# MCU.net
KiCad netlist of a schematic drawn in Altium Designer
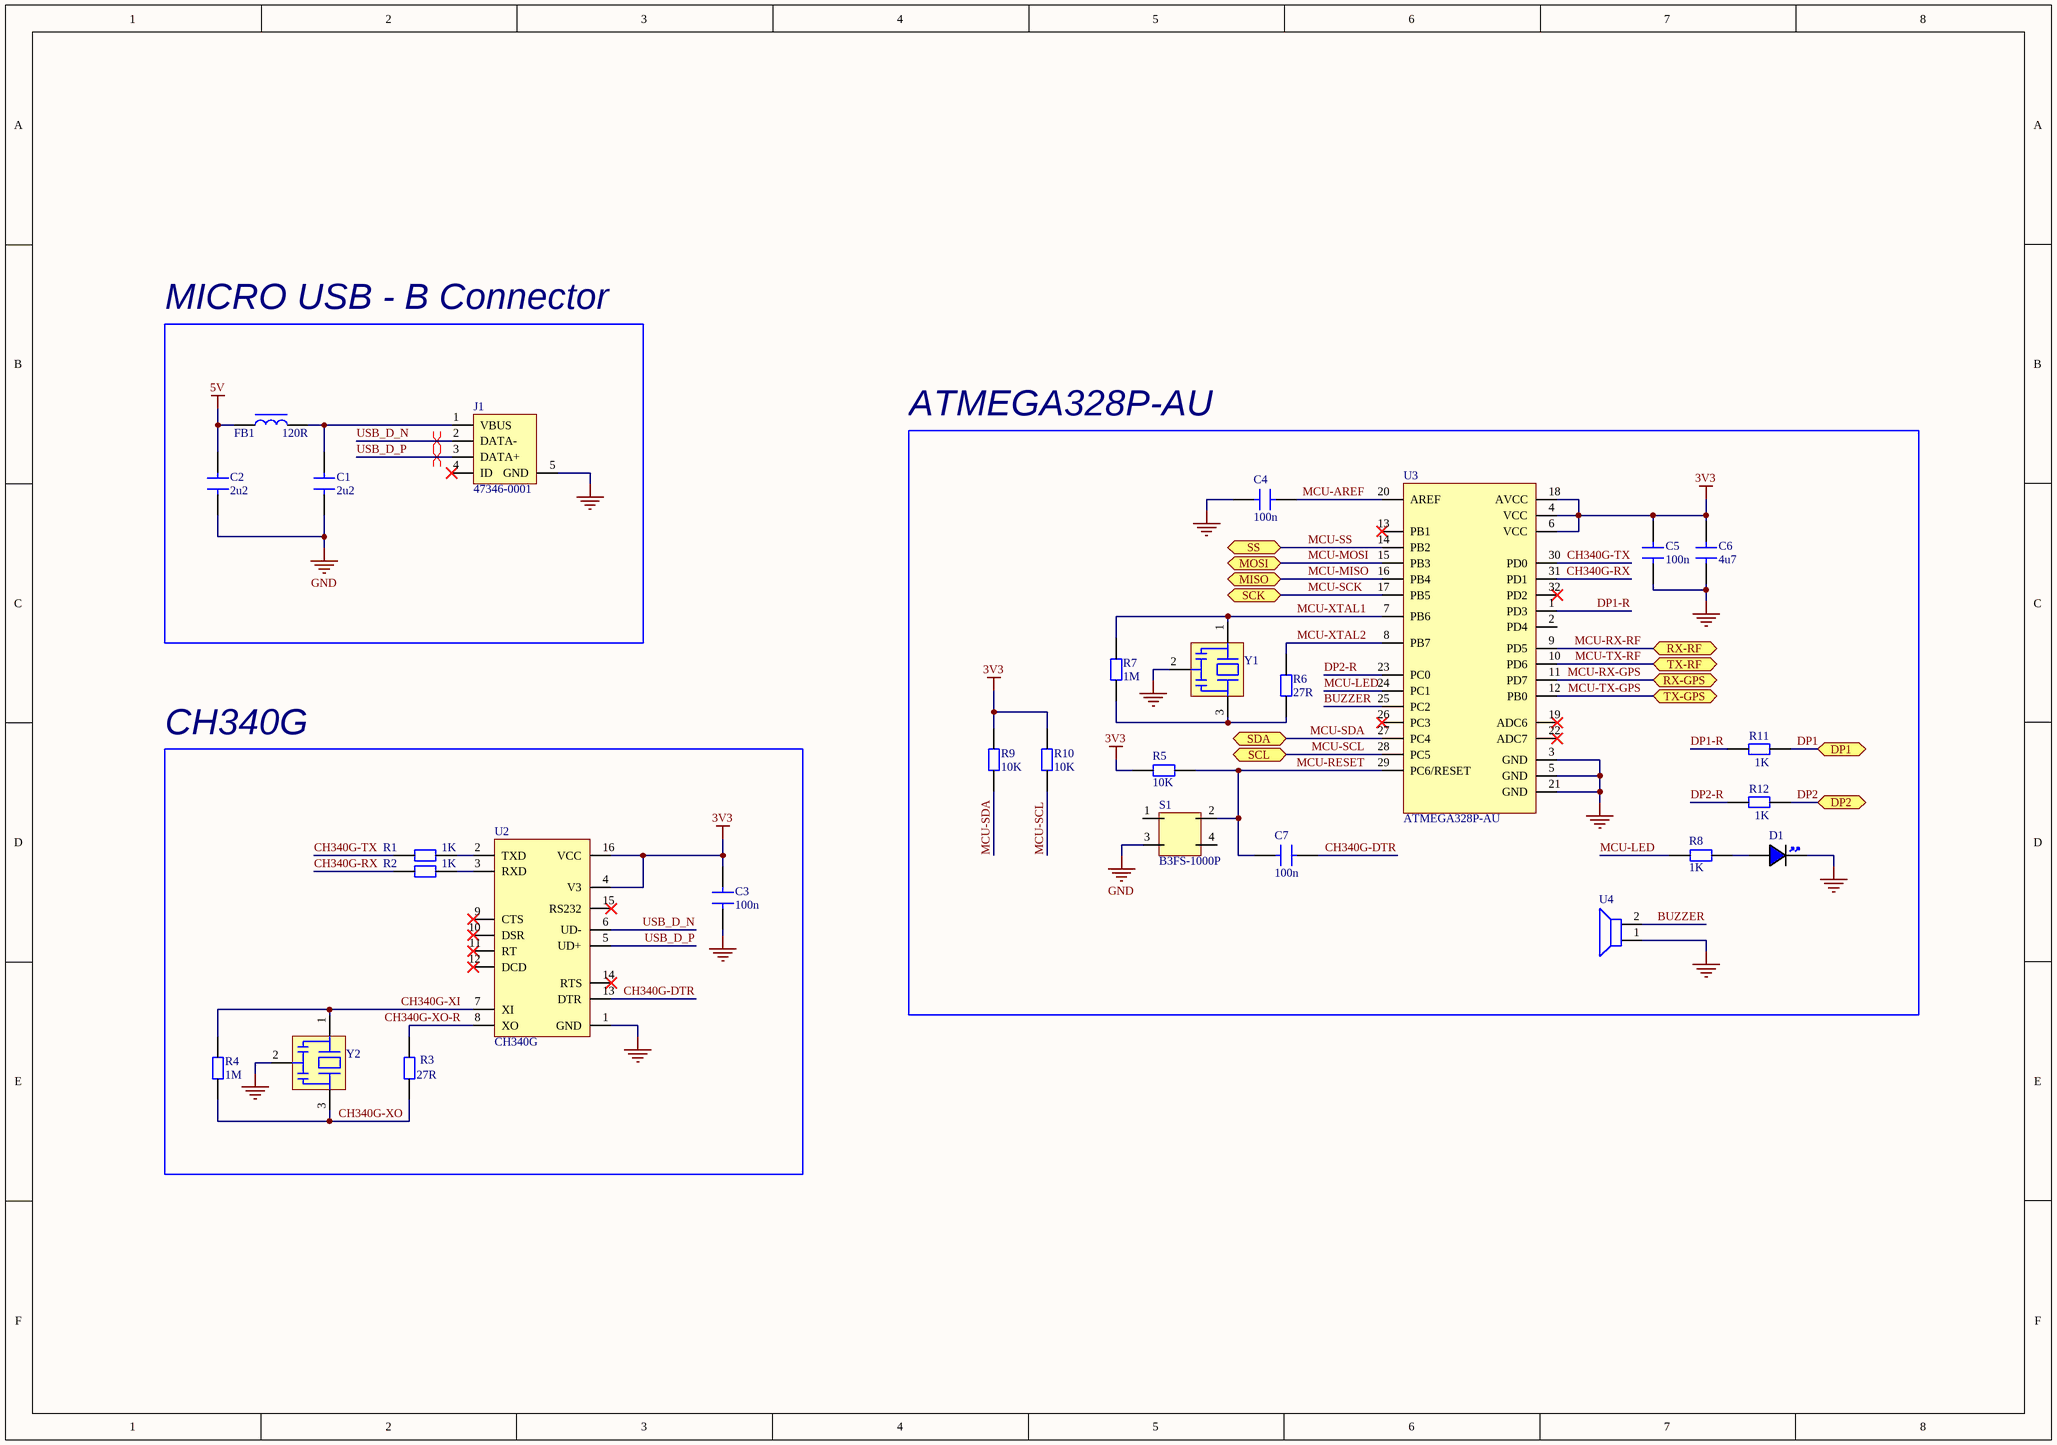
[diagram p0: MCU.SchDoc]

(export (version "E")
  (design (tool "Eeschema 10.0.6"))
  (components
    (comp (ref "C1")
      (value "2u2")
      (footprint "CAP 0603")
      (description "Capacitor SMD 0603 50V")
      (libsource (lib "Schlib") (part "CAP 0603 50V"))
    )
    (comp (ref "C2")
      (value "2u2")
      (footprint "CAP 0603")
      (description "Capacitor SMD 0603 50V")
      (libsource (lib "Schlib") (part "CAP 0603 50V"))
    )
    (comp (ref "C3")
      (value "100n")
      (footprint "CAP 0603")
      (description "Capacitor SMD 0603 50V")
      (libsource (lib "Schlib") (part "CAP 0603 50V"))
    )
    (comp (ref "C4")
      (value "100n")
      (footprint "CAP 0603")
      (description "Capacitor SMD 0603 50V")
      (libsource (lib "Schlib") (part "CAP 0603 50V"))
    )
    (comp (ref "C5")
      (value "100n")
      (footprint "CAP 0603")
      (description "Capacitor SMD 0603 50V")
      (libsource (lib "Schlib") (part "CAP 0603 50V"))
    )
    (comp (ref "C6")
      (value "4u7")
      (footprint "CAP 0603")
      (description "Capacitor SMD 0603 50V")
      (libsource (lib "Schlib") (part "CAP 0603 50V"))
    )
    (comp (ref "C7")
      (value "100n")
      (footprint "CAP 0603")
      (description "Capacitor SMD 0603 50V")
      (libsource (lib "Schlib") (part "CAP 0603 50V"))
    )
    (comp (ref "D1")
      (value "LED 0805 BLUE")
      (footprint "LED 0805 BLUE")
      (description "LED 0805 GREEN SMD")
      (libsource (lib "Schlib") (part "LED 0805 BLUE"))
    )
    (comp (ref "FB1")
      (value "120R")
      (footprint "FB 0805")
      (description "Ferrite Bead SMD 0805")
      (libsource (lib "Schlib") (part "FB 0805"))
    )
    (comp (ref "J1")
      (value "47346-0001")
      (footprint "MOLEX_47346-0001")
      (description "Micro-USB B Receptacle with Flange, Bottom Mount, Surface Mount, Lead-Free")
      (fields (field (name "MANUFACTURER") "Molex"))
      (libsource (lib "Schlib") (part "47346-0001"))
    )
    (comp (ref "R1")
      (value "1K")
      (footprint "RES 0603")
      (description "Resistor SMD 0603")
      (libsource (lib "Schlib") (part "RES 0603"))
    )
    (comp (ref "R2")
      (value "1K")
      (footprint "RES 0603")
      (description "Resistor SMD 0603")
      (libsource (lib "Schlib") (part "RES 0603"))
    )
    (comp (ref "R3")
      (value "27R")
      (footprint "RES 0603")
      (description "Resistor SMD 0603")
      (libsource (lib "Schlib") (part "RES 0603"))
    )
    (comp (ref "R4")
      (value "1M")
      (footprint "RES 0603")
      (description "Resistor SMD 0603")
      (libsource (lib "Schlib") (part "RES 0603"))
    )
    (comp (ref "R5")
      (value "10K")
      (footprint "RES 0603")
      (description "Resistor SMD 0603")
      (libsource (lib "Schlib") (part "RES 0603"))
    )
    (comp (ref "R6")
      (value "27R")
      (footprint "RES 0603")
      (description "Resistor SMD 0603")
      (libsource (lib "Schlib") (part "RES 0603"))
    )
    (comp (ref "R7")
      (value "1M")
      (footprint "RES 0603")
      (description "Resistor SMD 0603")
      (libsource (lib "Schlib") (part "RES 0603"))
    )
    (comp (ref "R8")
      (value "1K")
      (footprint "RES 0603")
      (description "Resistor SMD 0603")
      (libsource (lib "Schlib") (part "RES 0603"))
    )
    (comp (ref "R9")
      (value "10K")
      (footprint "RES 0603")
      (description "Resistor SMD 0603")
      (libsource (lib "Schlib") (part "RES 0603"))
    )
    (comp (ref "R10")
      (value "10K")
      (footprint "RES 0603")
      (description "Resistor SMD 0603")
      (libsource (lib "Schlib") (part "RES 0603"))
    )
    (comp (ref "R11")
      (value "1K")
      (footprint "RES 0603")
      (description "Resistor SMD 0603")
      (libsource (lib "Schlib") (part "RES 0603"))
    )
    (comp (ref "R12")
      (value "1K")
      (footprint "RES 0603")
      (description "Resistor SMD 0603")
      (libsource (lib "Schlib") (part "RES 0603"))
    )
    (comp (ref "S1")
      (value "B3FS-1000P")
      (footprint "B3FS-1000P")
      (description "Switch Tactile N.O. SPST Flat Round Button Gull Wing 0.05A 24VDC 0.98N SMD T/R")
      (fields (field (name "MANUFACTURER") "Omron"))
      (libsource (lib "Schlib") (part "B3FS-1000P"))
    )
    (comp (ref "U2")
      (value "CH340G")
      (footprint "CH340G")
      (description "USB Interface Integrated Circuit")
      (libsource (lib "Schlib") (part "CH340G"))
    )
    (comp (ref "U3")
      (value "ATMEGA328P-AU")
      (footprint "ATMEGA328P-AU")
      (description "8-bit AVR MCU, 32 KB, 2048 Bytes, 20 MHz, 1.8 to 5.5V, TQFP-32, RoHS")
      (fields (field (name "MANUFACTURER") "Microchip"))
      (libsource (lib "Schlib") (part "ATMEGA328P-AU"))
    )
    (comp (ref "U4")
      (value "PS1240P02BT")
      (footprint "PS1240P02BT")
      (description "Audio Buzzer Piezo 30Vo-p 3Vo-p 70dBA Through Hole Pin Ammo")
      (fields (field (name "MANUFACTURER") "TDK"))
      (libsource (lib "Schlib") (part "PS1240P02BT"))
    )
    (comp (ref "Y1")
      (value "CSTNE16M0V53Z000R0")
      (footprint "CSTNE16M0V53Z000R0")
      (description "Ceramic Resonator 16MHz ±0.5% (Tol) ±0.3% (Stability) 15pF 40Ohm 3-Pin CSMD T/R")
      (fields (field (name "MANUFACTURER") "Murata"))
      (libsource (lib "Schlib") (part "CSTNE16M0V53Z000R0"))
    )
    (comp (ref "Y2")
      (value "CSTNE12M0G550000R0")
      (footprint "CSTNE16M0V53Z000R0")
      (description "Ceramic Resonator 12MHz ±0.5% (Tol ) ±0.2% (Stability) 33PF 30Ohm 3-Pin CSMD")
      (fields (field (name "MANUFACTURER") "Murata"))
      (libsource (lib "Schlib") (part "CSTNE12M0G550000R0"))
    )
  )
  (nets
    (net (code "1") (name "/BUZZER") (class "Default")
      (node (ref "U3") (pin "25") (pinfunction "PC2_25") (pintype "passive"))
      (node (ref "U4") (pin "2") (pinfunction "2_2") (pintype "passive"))
    )
    (net (code "2") (name "/CH340G-DTR") (class "Default")
      (node (ref "C7") (pin "1") (pinfunction "1_1") (pintype "passive"))
      (node (ref "U2") (pin "13") (pinfunction "DTR_13") (pintype "passive"))
    )
    (net (code "3") (name "/CH340G-RX") (class "Default")
      (node (ref "R2") (pin "2") (pinfunction "2_2") (pintype "passive"))
      (node (ref "U3") (pin "31") (pinfunction "PD1_31") (pintype "passive"))
    )
    (net (code "4") (name "/CH340G-TX") (class "Default")
      (node (ref "R1") (pin "2") (pinfunction "2_2") (pintype "passive"))
      (node (ref "U3") (pin "30") (pinfunction "PD0_30") (pintype "passive"))
    )
    (net (code "5") (name "/CH340G-XI") (class "Default")
      (node (ref "R4") (pin "2") (pinfunction "2_2") (pintype "passive"))
      (node (ref "U2") (pin "7") (pinfunction "XI_7") (pintype "passive"))
      (node (ref "Y2") (pin "1") (pinfunction "1_1") (pintype "passive"))
    )
    (net (code "6") (name "/CH340G-XO") (class "Default")
      (node (ref "R3") (pin "1") (pinfunction "1_1") (pintype "passive"))
      (node (ref "R4") (pin "1") (pinfunction "1_1") (pintype "passive"))
      (node (ref "Y2") (pin "3") (pinfunction "3_3") (pintype "passive"))
    )
    (net (code "7") (name "/CH340G-XO-R") (class "Default")
      (node (ref "R3") (pin "2") (pinfunction "2_2") (pintype "passive"))
      (node (ref "U2") (pin "8") (pinfunction "XO_8") (pintype "passive"))
    )
    (net (code "8") (name "/DP1") (class "Default")
      (node (ref "R11") (pin "2") (pinfunction "2_2") (pintype "passive"))
    )
    (net (code "9") (name "/DP1-R") (class "Default")
      (node (ref "R11") (pin "1") (pinfunction "1_1") (pintype "passive"))
      (node (ref "U3") (pin "1") (pinfunction "PD3_1") (pintype "passive"))
    )
    (net (code "10") (name "/DP2") (class "Default")
      (node (ref "R12") (pin "2") (pinfunction "2_2") (pintype "passive"))
    )
    (net (code "11") (name "/DP2-R") (class "Default")
      (node (ref "R12") (pin "1") (pinfunction "1_1") (pintype "passive"))
      (node (ref "U3") (pin "23") (pinfunction "PC0_23") (pintype "passive"))
    )
    (net (code "12") (name "/MCU-AREF") (class "Default")
      (node (ref "C4") (pin "1") (pinfunction "1_1") (pintype "passive"))
      (node (ref "U3") (pin "20") (pinfunction "AREF_20") (pintype "passive"))
    )
    (net (code "13") (name "/MCU-LED") (class "Default")
      (node (ref "R8") (pin "1") (pinfunction "1_1") (pintype "passive"))
      (node (ref "U3") (pin "24") (pinfunction "PC1_24") (pintype "passive"))
    )
    (net (code "14") (name "/MCU-MISO") (class "Default")
      (node (ref "U3") (pin "16") (pinfunction "PB4_16") (pintype "passive"))
    )
    (net (code "15") (name "/MCU-MOSI") (class "Default")
      (node (ref "U3") (pin "15") (pinfunction "PB3_15") (pintype "passive"))
    )
    (net (code "16") (name "/MCU-RESET") (class "Default")
      (node (ref "C7") (pin "2") (pinfunction "2_2") (pintype "passive"))
      (node (ref "R5") (pin "2") (pinfunction "2_2") (pintype "passive"))
      (node (ref "S1") (pin "2") (pinfunction "2_2") (pintype "passive"))
      (node (ref "U3") (pin "29") (pinfunction "PC6/RESET_29") (pintype "passive"))
    )
    (net (code "17") (name "/MCU-RX-GPS") (class "Default")
      (node (ref "U3") (pin "11") (pinfunction "PD7_11") (pintype "passive"))
    )
    (net (code "18") (name "/MCU-RX-RF") (class "Default")
      (node (ref "U3") (pin "9") (pinfunction "PD5_9") (pintype "passive"))
    )
    (net (code "19") (name "/MCU-SCK") (class "Default")
      (node (ref "U3") (pin "17") (pinfunction "PB5_17") (pintype "passive"))
    )
    (net (code "20") (name "/MCU-SCL") (class "Default")
      (node (ref "R10") (pin "1") (pinfunction "1_1") (pintype "passive"))
      (node (ref "U3") (pin "28") (pinfunction "PC5_28") (pintype "passive"))
    )
    (net (code "21") (name "/MCU-SDA") (class "Default")
      (node (ref "R9") (pin "1") (pinfunction "1_1") (pintype "passive"))
      (node (ref "U3") (pin "27") (pinfunction "PC4_27") (pintype "passive"))
    )
    (net (code "22") (name "/MCU-SS") (class "Default")
      (node (ref "U3") (pin "14") (pinfunction "PB2_14") (pintype "passive"))
    )
    (net (code "23") (name "/MCU-TX-GPS") (class "Default")
      (node (ref "U3") (pin "12") (pinfunction "PB0_12") (pintype "passive"))
    )
    (net (code "24") (name "/MCU-TX-RF") (class "Default")
      (node (ref "U3") (pin "10") (pinfunction "PD6_10") (pintype "passive"))
    )
    (net (code "25") (name "/MCU-XTAL1") (class "Default")
      (node (ref "R7") (pin "2") (pinfunction "2_2") (pintype "passive"))
      (node (ref "U3") (pin "7") (pinfunction "PB6_7") (pintype "passive"))
      (node (ref "Y1") (pin "1") (pinfunction "1_1") (pintype "passive"))
    )
    (net (code "26") (name "/MCU-XTAL2") (class "Default")
      (node (ref "R6") (pin "2") (pinfunction "2_2") (pintype "passive"))
      (node (ref "U3") (pin "8") (pinfunction "PB7_8") (pintype "passive"))
    )
    (net (code "27") (name "/USB_D_N") (class "Default")
      (node (ref "J1") (pin "2") (pinfunction "DATA-_2") (pintype "passive"))
      (node (ref "U2") (pin "6") (pinfunction "UD-_6") (pintype "passive"))
    )
    (net (code "28") (name "/USB_D_P") (class "Default")
      (node (ref "J1") (pin "3") (pinfunction "DATA+_3") (pintype "passive"))
      (node (ref "U2") (pin "5") (pinfunction "UD+_5") (pintype "passive"))
    )
    (net (code "29") (name "3V3") (class "Default")
      (node (ref "C3") (pin "2") (pinfunction "2_2") (pintype "passive"))
      (node (ref "C5") (pin "2") (pinfunction "2_2") (pintype "passive"))
      (node (ref "C6") (pin "2") (pinfunction "2_2") (pintype "passive"))
      (node (ref "R10") (pin "2") (pinfunction "2_2") (pintype "passive"))
      (node (ref "R5") (pin "1") (pinfunction "1_1") (pintype "passive"))
      (node (ref "R9") (pin "2") (pinfunction "2_2") (pintype "passive"))
      (node (ref "U2") (pin "16") (pinfunction "VCC_16") (pintype "passive"))
      (node (ref "U2") (pin "4") (pinfunction "V3_4") (pintype "passive"))
      (node (ref "U3") (pin "18") (pinfunction "AVCC_18") (pintype "passive"))
      (node (ref "U3") (pin "4") (pinfunction "VCC_4") (pintype "passive"))
      (node (ref "U3") (pin "6") (pinfunction "VCC_6") (pintype "passive"))
    )
    (net (code "30") (name "5V") (class "Default")
      (node (ref "C2") (pin "1") (pinfunction "1_1") (pintype "passive"))
      (node (ref "FB1") (pin "1") (pintype "passive"))
    )
    (net (code "31") (name "GND") (class "Default")
      (node (ref "C1") (pin "2") (pinfunction "2_2") (pintype "passive"))
      (node (ref "C2") (pin "2") (pinfunction "2_2") (pintype "passive"))
      (node (ref "C3") (pin "1") (pinfunction "1_1") (pintype "passive"))
      (node (ref "C4") (pin "2") (pinfunction "2_2") (pintype "passive"))
      (node (ref "C5") (pin "1") (pinfunction "1_1") (pintype "passive"))
      (node (ref "C6") (pin "1") (pinfunction "1_1") (pintype "passive"))
      (node (ref "D1") (pin "K") (pinfunction "K_K") (pintype "passive"))
      (node (ref "J1") (pin "5") (pinfunction "GND_5") (pintype "passive"))
      (node (ref "S1") (pin "3") (pinfunction "3_3") (pintype "passive"))
      (node (ref "U2") (pin "1") (pinfunction "GND_1") (pintype "passive"))
      (node (ref "U3") (pin "21") (pinfunction "GND_21") (pintype "passive"))
      (node (ref "U3") (pin "3") (pinfunction "GND_3") (pintype "passive"))
      (node (ref "U3") (pin "5") (pinfunction "GND_5") (pintype "passive"))
      (node (ref "U4") (pin "1") (pinfunction "1_1") (pintype "passive"))
      (node (ref "Y1") (pin "2") (pinfunction "2_2") (pintype "passive"))
      (node (ref "Y2") (pin "2") (pinfunction "2_2") (pintype "passive"))
    )
    (net (code "32") (name "Net-(D1-PadA)") (class "Default")
      (node (ref "D1") (pin "A") (pinfunction "A_A") (pintype "passive"))
      (node (ref "R8") (pin "2") (pinfunction "2_2") (pintype "passive"))
    )
    (net (code "33") (name "Net-(J1-VBUS)") (class "Default")
      (node (ref "C1") (pin "1") (pinfunction "1_1") (pintype "passive"))
      (node (ref "FB1") (pin "2") (pintype "passive"))
      (node (ref "J1") (pin "1") (pinfunction "VBUS_1") (pintype "passive"))
    )
    (net (code "34") (name "Net-(R6-Pad1)") (class "Default")
      (node (ref "R6") (pin "1") (pinfunction "1_1") (pintype "passive"))
      (node (ref "R7") (pin "1") (pinfunction "1_1") (pintype "passive"))
      (node (ref "Y1") (pin "3") (pinfunction "3_3") (pintype "passive"))
    )
    (net (code "35") (name "Net-(U2-RXD)") (class "Default")
      (node (ref "R2") (pin "1") (pinfunction "1_1") (pintype "passive"))
      (node (ref "U2") (pin "3") (pinfunction "RXD_3") (pintype "passive"))
    )
    (net (code "36") (name "Net-(U2-TXD)") (class "Default")
      (node (ref "R1") (pin "1") (pinfunction "1_1") (pintype "passive"))
      (node (ref "U2") (pin "2") (pinfunction "TXD_2") (pintype "passive"))
    )
    (net (code "37") (name "unconnected-(J1-ID-Pad4)") (class "Default")
      (node (ref "J1") (pin "4") (pinfunction "ID_4") (pintype "passive+no_connect"))
    )
    (net (code "38") (name "unconnected-(S1-Pad1)") (class "Default")
      (node (ref "S1") (pin "1") (pinfunction "1_1") (pintype "passive"))
    )
    (net (code "39") (name "unconnected-(S1-Pad4)") (class "Default")
      (node (ref "S1") (pin "4") (pinfunction "4_4") (pintype "passive"))
    )
    (net (code "40") (name "unconnected-(U2-CTS-Pad9)") (class "Default")
      (node (ref "U2") (pin "9") (pinfunction "CTS_9") (pintype "passive+no_connect"))
    )
    (net (code "41") (name "unconnected-(U2-DCD-Pad12)") (class "Default")
      (node (ref "U2") (pin "12") (pinfunction "DCD_12") (pintype "passive+no_connect"))
    )
    (net (code "42") (name "unconnected-(U2-DSR-Pad10)") (class "Default")
      (node (ref "U2") (pin "10") (pinfunction "DSR_10") (pintype "passive+no_connect"))
    )
    (net (code "43") (name "unconnected-(U2-RS232-Pad15)") (class "Default")
      (node (ref "U2") (pin "15") (pinfunction "RS232_15") (pintype "passive+no_connect"))
    )
    (net (code "44") (name "unconnected-(U2-RT-Pad11)") (class "Default")
      (node (ref "U2") (pin "11") (pinfunction "RT_11") (pintype "passive+no_connect"))
    )
    (net (code "45") (name "unconnected-(U2-RTS-Pad14)") (class "Default")
      (node (ref "U2") (pin "14") (pinfunction "RTS_14") (pintype "passive+no_connect"))
    )
    (net (code "46") (name "unconnected-(U3-ADC6-Pad19)") (class "Default")
      (node (ref "U3") (pin "19") (pinfunction "ADC6_19") (pintype "passive+no_connect"))
    )
    (net (code "47") (name "unconnected-(U3-ADC7-Pad22)") (class "Default")
      (node (ref "U3") (pin "22") (pinfunction "ADC7_22") (pintype "passive+no_connect"))
    )
    (net (code "48") (name "unconnected-(U3-PB1-Pad13)") (class "Default")
      (node (ref "U3") (pin "13") (pinfunction "PB1_13") (pintype "passive+no_connect"))
    )
    (net (code "49") (name "unconnected-(U3-PC3-Pad26)") (class "Default")
      (node (ref "U3") (pin "26") (pinfunction "PC3_26") (pintype "passive+no_connect"))
    )
    (net (code "50") (name "unconnected-(U3-PD2-Pad32)") (class "Default")
      (node (ref "U3") (pin "32") (pinfunction "PD2_32") (pintype "passive+no_connect"))
    )
    (net (code "51") (name "unconnected-(U3-PD4-Pad2)") (class "Default")
      (node (ref "U3") (pin "2") (pinfunction "PD4_2") (pintype "passive"))
    )
  )
)
